# Interfaces.net
KiCad netlist of a schematic drawn in Altium Designer
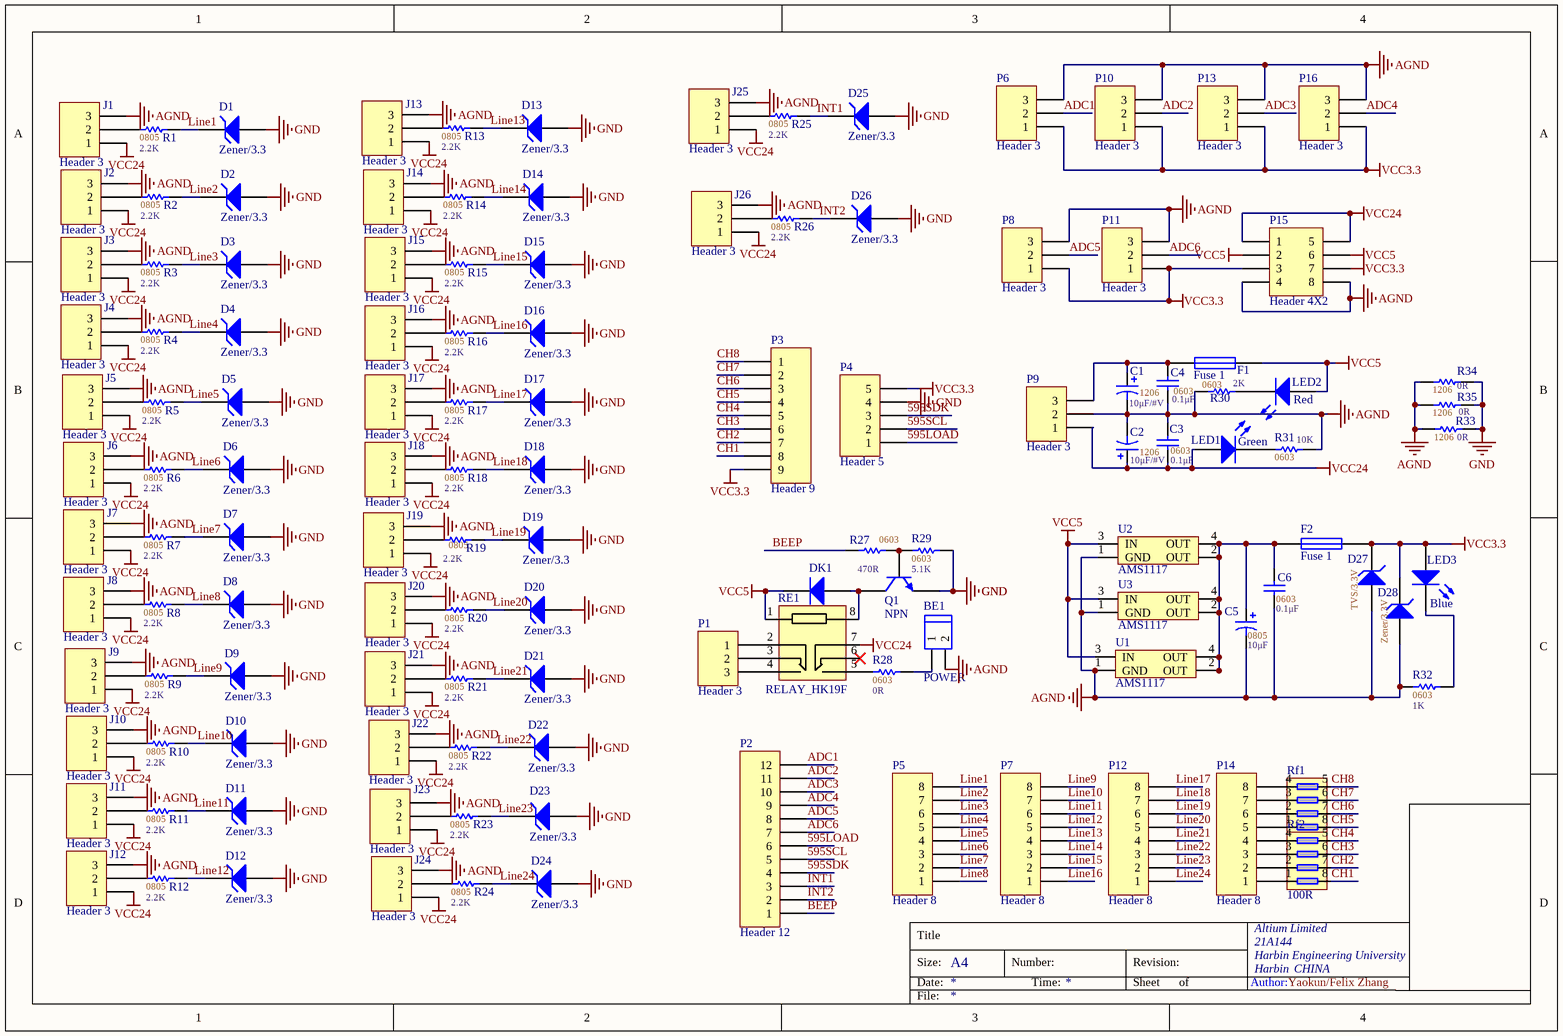
[diagram p0: Interfaces.SchDoc]

(export (version "E")
  (design (tool "Eeschema 10.0.6"))
  (components
    (comp (ref "BE1")
      (value "POWER")
      (footprint "H2_Push_out3.81")
      (libsource (lib "Belong_to_Kongkong") (part "HEAD2"))
    )
    (comp (ref "C1")
      (value "10μF/#V")
      (footprint "CAP_1206")
      (description "Polarized Capacitor (Axial)")
      (fields (field (name "PACKAGEREFERENCE") "1206") (field (name "Comment") "Polar"))
      (libsource (lib "Belong_to_Kongkong") (part "Cap Pol"))
    )
    (comp (ref "C2")
      (value "10μF/#V")
      (footprint "CAP_1206")
      (description "Polarized Capacitor (Axial)")
      (fields (field (name "PACKAGEREFERENCE") "1206") (field (name "Comment") "Polar"))
      (libsource (lib "Belong_to_Kongkong") (part "Cap Pol"))
    )
    (comp (ref "C3")
      (value "0.1μF")
      (footprint "CAP_0603_16*08")
      (description "Capacitor")
      (fields (field (name "PACKAGEREFERENCE") "0603") (field (name "Comment") "0603"))
      (libsource (lib "Belong_to_Kongkong") (part "Cap"))
    )
    (comp (ref "C4")
      (value "0.1μF")
      (footprint "CAP_0603_16*08")
      (description "Capacitor")
      (fields (field (name "PACKAGEREFERENCE") "0603") (field (name "Comment") "0603"))
      (libsource (lib "Belong_to_Kongkong") (part "Cap"))
    )
    (comp (ref "C5")
      (value "10μF")
      (footprint "CAP_0805_20*12")
      (description "Polarized Capacitor (Axial)")
      (fields (field (name "PACKAGEREFERENCE") "0805") (field (name "Comment") "Polar"))
      (libsource (lib "Belong_to_Kongkong") (part "Cap Pol"))
    )
    (comp (ref "C6")
      (value "0.1μF")
      (footprint "CAP_0603_16*08")
      (description "Capacitor")
      (fields (field (name "PACKAGEREFERENCE") "0603") (field (name "Comment") "0603"))
      (libsource (lib "Belong_to_Kongkong") (part "Cap"))
    )
    (comp (ref "D1")
      (value "Zener/3.3")
      (footprint "SOD323")
      (description "Zener Diode")
      (libsource (lib "Belong_to_Kongkong") (part "D Zener"))
    )
    (comp (ref "D2")
      (value "Zener/3.3")
      (footprint "SOD323")
      (description "Zener Diode")
      (libsource (lib "Belong_to_Kongkong") (part "D Zener"))
    )
    (comp (ref "D3")
      (value "Zener/3.3")
      (footprint "SOD323")
      (description "Zener Diode")
      (libsource (lib "Belong_to_Kongkong") (part "D Zener"))
    )
    (comp (ref "D4")
      (value "Zener/3.3")
      (footprint "SOD323")
      (description "Zener Diode")
      (libsource (lib "Belong_to_Kongkong") (part "D Zener"))
    )
    (comp (ref "D5")
      (value "Zener/3.3")
      (footprint "SOD323")
      (description "Zener Diode")
      (libsource (lib "Belong_to_Kongkong") (part "D Zener"))
    )
    (comp (ref "D6")
      (value "Zener/3.3")
      (footprint "SOD323")
      (description "Zener Diode")
      (libsource (lib "Belong_to_Kongkong") (part "D Zener"))
    )
    (comp (ref "D7")
      (value "Zener/3.3")
      (footprint "SOD323")
      (description "Zener Diode")
      (libsource (lib "Belong_to_Kongkong") (part "D Zener"))
    )
    (comp (ref "D8")
      (value "Zener/3.3")
      (footprint "SOD323")
      (description "Zener Diode")
      (libsource (lib "Belong_to_Kongkong") (part "D Zener"))
    )
    (comp (ref "D9")
      (value "Zener/3.3")
      (footprint "SOD323")
      (description "Zener Diode")
      (libsource (lib "Belong_to_Kongkong") (part "D Zener"))
    )
    (comp (ref "D10")
      (value "Zener/3.3")
      (footprint "SOD323")
      (description "Zener Diode")
      (libsource (lib "Belong_to_Kongkong") (part "D Zener"))
    )
    (comp (ref "D11")
      (value "Zener/3.3")
      (footprint "SOD323")
      (description "Zener Diode")
      (libsource (lib "Belong_to_Kongkong") (part "D Zener"))
    )
    (comp (ref "D12")
      (value "Zener/3.3")
      (footprint "SOD323")
      (description "Zener Diode")
      (libsource (lib "Belong_to_Kongkong") (part "D Zener"))
    )
    (comp (ref "D13")
      (value "Zener/3.3")
      (footprint "SOD323")
      (description "Zener Diode")
      (libsource (lib "Belong_to_Kongkong") (part "D Zener"))
    )
    (comp (ref "D14")
      (value "Zener/3.3")
      (footprint "SOD323")
      (description "Zener Diode")
      (libsource (lib "Belong_to_Kongkong") (part "D Zener"))
    )
    (comp (ref "D15")
      (value "Zener/3.3")
      (footprint "SOD323")
      (description "Zener Diode")
      (libsource (lib "Belong_to_Kongkong") (part "D Zener"))
    )
    (comp (ref "D16")
      (value "Zener/3.3")
      (footprint "SOD323")
      (description "Zener Diode")
      (libsource (lib "Belong_to_Kongkong") (part "D Zener"))
    )
    (comp (ref "D17")
      (value "Zener/3.3")
      (footprint "SOD323")
      (description "Zener Diode")
      (libsource (lib "Belong_to_Kongkong") (part "D Zener"))
    )
    (comp (ref "D18")
      (value "Zener/3.3")
      (footprint "SOD323")
      (description "Zener Diode")
      (libsource (lib "Belong_to_Kongkong") (part "D Zener"))
    )
    (comp (ref "D19")
      (value "Zener/3.3")
      (footprint "SOD323")
      (description "Zener Diode")
      (libsource (lib "Belong_to_Kongkong") (part "D Zener"))
    )
    (comp (ref "D20")
      (value "Zener/3.3")
      (footprint "SOD323")
      (description "Zener Diode")
      (libsource (lib "Belong_to_Kongkong") (part "D Zener"))
    )
    (comp (ref "D21")
      (value "Zener/3.3")
      (footprint "SOD323")
      (description "Zener Diode")
      (libsource (lib "Belong_to_Kongkong") (part "D Zener"))
    )
    (comp (ref "D22")
      (value "Zener/3.3")
      (footprint "SOD323")
      (description "Zener Diode")
      (libsource (lib "Belong_to_Kongkong") (part "D Zener"))
    )
    (comp (ref "D23")
      (value "Zener/3.3")
      (footprint "SOD323")
      (description "Zener Diode")
      (libsource (lib "Belong_to_Kongkong") (part "D Zener"))
    )
    (comp (ref "D24")
      (value "Zener/3.3")
      (footprint "SOD323")
      (description "Zener Diode")
      (libsource (lib "Belong_to_Kongkong") (part "D Zener"))
    )
    (comp (ref "D25")
      (value "Zener/3.3")
      (footprint "SOD323")
      (description "Zener Diode")
      (libsource (lib "Belong_to_Kongkong") (part "D Zener"))
    )
    (comp (ref "D26")
      (value "Zener/3.3")
      (footprint "SOD323")
      (description "Zener Diode")
      (libsource (lib "Belong_to_Kongkong") (part "D Zener"))
    )
    (comp (ref "D27")
      (value "TVS/3.3V")
      (footprint "SOD523")
      (description "Zener Diode")
      (libsource (lib "Belong_to_Kongkong") (part "D Zener"))
    )
    (comp (ref "D28")
      (value "Zener/3.3V")
      (footprint "SOD323")
      (description "Zener Diode")
      (libsource (lib "Belong_to_Kongkong") (part "D Zener"))
    )
    (comp (ref "DK1")
      (value "Diode")
      (footprint "Diode1206")
      (description "Default Diode")
      (libsource (lib "Belong_to_Kongkong") (part "Diode"))
    )
    (comp (ref "F1")
      (value "Fuse 1")
      (footprint "FUSE3.5*5.5")
      (description "Fuse")
      (libsource (lib "Belong_to_Kongkong") (part "Fuse 1"))
    )
    (comp (ref "F2")
      (value "Fuse 1")
      (footprint "FUSE3.5*5.5")
      (description "Fuse")
      (libsource (lib "Belong_to_Kongkong") (part "Fuse 1"))
    )
    (comp (ref "J1")
      (value "Header 3")
      (footprint "P3_OUT")
      (description "Header, 3-Pin")
      (libsource (lib "Belong_to_Kongkong") (part "Header 3"))
    )
    (comp (ref "J2")
      (value "Header 3")
      (footprint "P3_OUT")
      (description "Header, 3-Pin")
      (libsource (lib "Belong_to_Kongkong") (part "Header 3"))
    )
    (comp (ref "J3")
      (value "Header 3")
      (footprint "P3_OUT")
      (description "Header, 3-Pin")
      (libsource (lib "Belong_to_Kongkong") (part "Header 3"))
    )
    (comp (ref "J4")
      (value "Header 3")
      (footprint "P3_OUT")
      (description "Header, 3-Pin")
      (libsource (lib "Belong_to_Kongkong") (part "Header 3"))
    )
    (comp (ref "J5")
      (value "Header 3")
      (footprint "P3_OUT")
      (description "Header, 3-Pin")
      (libsource (lib "Belong_to_Kongkong") (part "Header 3"))
    )
    (comp (ref "J6")
      (value "Header 3")
      (footprint "P3_OUT")
      (description "Header, 3-Pin")
      (libsource (lib "Belong_to_Kongkong") (part "Header 3"))
    )
    (comp (ref "J7")
      (value "Header 3")
      (footprint "P3_OUT")
      (description "Header, 3-Pin")
      (libsource (lib "Belong_to_Kongkong") (part "Header 3"))
    )
    (comp (ref "J8")
      (value "Header 3")
      (footprint "P3_OUT")
      (description "Header, 3-Pin")
      (libsource (lib "Belong_to_Kongkong") (part "Header 3"))
    )
    (comp (ref "J9")
      (value "Header 3")
      (footprint "P3_OUT")
      (description "Header, 3-Pin")
      (libsource (lib "Belong_to_Kongkong") (part "Header 3"))
    )
    (comp (ref "J10")
      (value "Header 3")
      (footprint "P3_OUT")
      (description "Header, 3-Pin")
      (libsource (lib "Belong_to_Kongkong") (part "Header 3"))
    )
    (comp (ref "J11")
      (value "Header 3")
      (footprint "P3_OUT")
      (description "Header, 3-Pin")
      (libsource (lib "Belong_to_Kongkong") (part "Header 3"))
    )
    (comp (ref "J12")
      (value "Header 3")
      (footprint "P3_OUT")
      (description "Header, 3-Pin")
      (libsource (lib "Belong_to_Kongkong") (part "Header 3"))
    )
    (comp (ref "J13")
      (value "Header 3")
      (footprint "P3_OUT")
      (description "Header, 3-Pin")
      (libsource (lib "Belong_to_Kongkong") (part "Header 3"))
    )
    (comp (ref "J14")
      (value "Header 3")
      (footprint "P3_OUT")
      (description "Header, 3-Pin")
      (libsource (lib "Belong_to_Kongkong") (part "Header 3"))
    )
    (comp (ref "J15")
      (value "Header 3")
      (footprint "P3_OUT")
      (description "Header, 3-Pin")
      (libsource (lib "Belong_to_Kongkong") (part "Header 3"))
    )
    (comp (ref "J16")
      (value "Header 3")
      (footprint "P3_OUT")
      (description "Header, 3-Pin")
      (libsource (lib "Belong_to_Kongkong") (part "Header 3"))
    )
    (comp (ref "J17")
      (value "Header 3")
      (footprint "P3_OUT")
      (description "Header, 3-Pin")
      (libsource (lib "Belong_to_Kongkong") (part "Header 3"))
    )
    (comp (ref "J18")
      (value "Header 3")
      (footprint "P3")
      (description "Header, 3-Pin")
      (libsource (lib "Belong_to_Kongkong") (part "Header 3"))
    )
    (comp (ref "J19")
      (value "Header 3")
      (footprint "P3")
      (description "Header, 3-Pin")
      (libsource (lib "Belong_to_Kongkong") (part "Header 3"))
    )
    (comp (ref "J20")
      (value "Header 3")
      (footprint "P3")
      (description "Header, 3-Pin")
      (libsource (lib "Belong_to_Kongkong") (part "Header 3"))
    )
    (comp (ref "J21")
      (value "Header 3")
      (footprint "P3")
      (description "Header, 3-Pin")
      (libsource (lib "Belong_to_Kongkong") (part "Header 3"))
    )
    (comp (ref "J22")
      (value "Header 3")
      (footprint "P3")
      (description "Header, 3-Pin")
      (libsource (lib "Belong_to_Kongkong") (part "Header 3"))
    )
    (comp (ref "J23")
      (value "Header 3")
      (footprint "P3")
      (description "Header, 3-Pin")
      (libsource (lib "Belong_to_Kongkong") (part "Header 3"))
    )
    (comp (ref "J24")
      (value "Header 3")
      (footprint "P3")
      (description "Header, 3-Pin")
      (libsource (lib "Belong_to_Kongkong") (part "Header 3"))
    )
    (comp (ref "J25")
      (value "Header 3")
      (footprint "P3_OUT")
      (description "Header, 3-Pin")
      (libsource (lib "Belong_to_Kongkong") (part "Header 3"))
    )
    (comp (ref "J26")
      (value "Header 3")
      (footprint "P3_OUT")
      (description "Header, 3-Pin")
      (libsource (lib "Belong_to_Kongkong") (part "Header 3"))
    )
    (comp (ref "LED1")
      (value "Green")
      (footprint "LED_0805")
      (description "Typical RED, GREEN, YELLOW, AMBER GaAs LED")
      (libsource (lib "Belong_to_Kongkong") (part "LED"))
    )
    (comp (ref "LED2")
      (value "Red")
      (footprint "LED_0805")
      (description "Typical RED, GREEN, YELLOW, AMBER GaAs LED")
      (libsource (lib "Belong_to_Kongkong") (part "LED"))
    )
    (comp (ref "LED3")
      (value "Blue")
      (footprint "LED_0805")
      (description "Typical RED, GREEN, YELLOW, AMBER GaAs LED")
      (libsource (lib "Belong_to_Kongkong") (part "LED"))
    )
    (comp (ref "P1")
      (value "Header 3")
      (footprint "P3_OUT")
      (description "Header, 3-Pin")
      (libsource (lib "") (part "Header 3_1"))
    )
    (comp (ref "P2")
      (value "Header 12")
      (footprint "P12_OUT")
      (description "Header, 12-Pin")
      (libsource (lib "Belong_to_Kongkong") (part "Header 12"))
    )
    (comp (ref "P3")
      (value "Header 9")
      (footprint "P9")
      (description "Header, 9-Pin")
      (libsource (lib "Belong_to_Kongkong") (part "Header 9"))
    )
    (comp (ref "P4")
      (value "Header 5")
      (footprint "Header5_KF2510")
      (description "Header, 5-Pin")
      (libsource (lib "Belong_to_Kongkong") (part "Header 5"))
    )
    (comp (ref "P5")
      (value "Header 8")
      (footprint "P8_OUT")
      (description "Header, 8-Pin")
      (libsource (lib "Belong_to_Kongkong") (part "Header 8"))
    )
    (comp (ref "P6")
      (value "Header 3")
      (footprint "P3_OUT")
      (description "Header, 3-Pin")
      (libsource (lib "Belong_to_Kongkong") (part "Header 3"))
    )
    (comp (ref "P7")
      (value "Header 8")
      (footprint "P8_OUT")
      (description "Header, 8-Pin")
      (libsource (lib "Belong_to_Kongkong") (part "Header 8"))
    )
    (comp (ref "P8")
      (value "Header 3")
      (footprint "P3")
      (description "Header, 3-Pin")
      (libsource (lib "Belong_to_Kongkong") (part "Header 3"))
    )
    (comp (ref "P9")
      (value "Header 3")
      (footprint "Header3_HC5.08")
      (description "Header, 3-Pin")
      (libsource (lib "Belong_to_Kongkong") (part "Header 3"))
    )
    (comp (ref "P10")
      (value "Header 3")
      (footprint "P3_OUT")
      (description "Header, 3-Pin")
      (libsource (lib "Belong_to_Kongkong") (part "Header 3"))
    )
    (comp (ref "P11")
      (value "Header 3")
      (footprint "P3")
      (description "Header, 3-Pin")
      (libsource (lib "Belong_to_Kongkong") (part "Header 3"))
    )
    (comp (ref "P12")
      (value "Header 8")
      (footprint "P8_OUT")
      (description "Header, 8-Pin")
      (libsource (lib "Belong_to_Kongkong") (part "Header 8"))
    )
    (comp (ref "P13")
      (value "Header 3")
      (footprint "P3_OUT")
      (description "Header, 3-Pin")
      (libsource (lib "Belong_to_Kongkong") (part "Header 3"))
    )
    (comp (ref "P14")
      (value "Header 8")
      (footprint "P8_OUT")
      (description "Header, 8-Pin")
      (libsource (lib "Belong_to_Kongkong") (part "Header 8"))
    )
    (comp (ref "P15")
      (value "Header 4X2")
      (footprint "HEADER2*4_PIN")
      (description "Header, 4-Pin, Dual row")
      (libsource (lib "Belong_to_Kongkong") (part "Header 4X2"))
    )
    (comp (ref "P16")
      (value "Header 3")
      (footprint "P3_OUT")
      (description "Header, 3-Pin")
      (libsource (lib "Belong_to_Kongkong") (part "Header 3"))
    )
    (comp (ref "Q1")
      (value "NPN")
      (footprint "SOT23_J3Y")
      (description "NPN Bipolar Transistor")
      (libsource (lib "Belong_to_Kongkong") (part "NPN"))
    )
    (comp (ref "R1")
      (value "2.2K")
      (footprint "RES_0805_20*12")
      (description "Resistor")
      (fields (field (name "PACKAGEREFERENCE") "0805") (field (name "Comment") "SMD"))
      (libsource (lib "Belong_to_Kongkong") (part "RES_SMD"))
    )
    (comp (ref "R2")
      (value "2.2K")
      (footprint "RES_0805_20*12")
      (description "Resistor")
      (fields (field (name "PACKAGEREFERENCE") "0805") (field (name "Comment") "SMD"))
      (libsource (lib "Belong_to_Kongkong") (part "RES_SMD"))
    )
    (comp (ref "R3")
      (value "2.2K")
      (footprint "RES_0805_20*12")
      (description "Resistor")
      (fields (field (name "PACKAGEREFERENCE") "0805") (field (name "Comment") "SMD"))
      (libsource (lib "Belong_to_Kongkong") (part "RES_SMD"))
    )
    (comp (ref "R4")
      (value "2.2K")
      (footprint "RES_0805_20*12")
      (description "Resistor")
      (fields (field (name "PACKAGEREFERENCE") "0805") (field (name "Comment") "SMD"))
      (libsource (lib "Belong_to_Kongkong") (part "RES_SMD"))
    )
    (comp (ref "R5")
      (value "2.2K")
      (footprint "RES_0805_20*12")
      (description "Resistor")
      (fields (field (name "PACKAGEREFERENCE") "0805") (field (name "Comment") "SMD"))
      (libsource (lib "Belong_to_Kongkong") (part "RES_SMD"))
    )
    (comp (ref "R6")
      (value "2.2K")
      (footprint "RES_0805_20*12")
      (description "Resistor")
      (fields (field (name "PACKAGEREFERENCE") "0805") (field (name "Comment") "SMD"))
      (libsource (lib "Belong_to_Kongkong") (part "RES_SMD"))
    )
    (comp (ref "R7")
      (value "2.2K")
      (footprint "RES_0805_20*12")
      (description "Resistor")
      (fields (field (name "PACKAGEREFERENCE") "0805") (field (name "Comment") "SMD"))
      (libsource (lib "Belong_to_Kongkong") (part "RES_SMD"))
    )
    (comp (ref "R8")
      (value "2.2K")
      (footprint "RES_0805_20*12")
      (description "Resistor")
      (fields (field (name "PACKAGEREFERENCE") "0805") (field (name "Comment") "SMD"))
      (libsource (lib "Belong_to_Kongkong") (part "RES_SMD"))
    )
    (comp (ref "R9")
      (value "2.2K")
      (footprint "RES_0805_20*12")
      (description "Resistor")
      (fields (field (name "PACKAGEREFERENCE") "0805") (field (name "Comment") "SMD"))
      (libsource (lib "Belong_to_Kongkong") (part "RES_SMD"))
    )
    (comp (ref "R10")
      (value "2.2K")
      (footprint "RES_0805_20*12")
      (description "Resistor")
      (fields (field (name "PACKAGEREFERENCE") "0805") (field (name "Comment") "SMD"))
      (libsource (lib "Belong_to_Kongkong") (part "RES_SMD"))
    )
    (comp (ref "R11")
      (value "2.2K")
      (footprint "RES_0805_20*12")
      (description "Resistor")
      (fields (field (name "PACKAGEREFERENCE") "0805") (field (name "Comment") "SMD"))
      (libsource (lib "Belong_to_Kongkong") (part "RES_SMD"))
    )
    (comp (ref "R12")
      (value "2.2K")
      (footprint "RES_0805_20*12")
      (description "Resistor")
      (fields (field (name "PACKAGEREFERENCE") "0805") (field (name "Comment") "SMD"))
      (libsource (lib "Belong_to_Kongkong") (part "RES_SMD"))
    )
    (comp (ref "R13")
      (value "2.2K")
      (footprint "RES_0805_20*12")
      (description "Resistor")
      (fields (field (name "PACKAGEREFERENCE") "0805") (field (name "Comment") "SMD"))
      (libsource (lib "Belong_to_Kongkong") (part "RES_SMD"))
    )
    (comp (ref "R14")
      (value "2.2K")
      (footprint "RES_0805_20*12")
      (description "Resistor")
      (fields (field (name "PACKAGEREFERENCE") "0805") (field (name "Comment") "SMD"))
      (libsource (lib "Belong_to_Kongkong") (part "RES_SMD"))
    )
    (comp (ref "R15")
      (value "2.2K")
      (footprint "RES_0805_20*12")
      (description "Resistor")
      (fields (field (name "PACKAGEREFERENCE") "0805") (field (name "Comment") "SMD"))
      (libsource (lib "Belong_to_Kongkong") (part "RES_SMD"))
    )
    (comp (ref "R16")
      (value "2.2K")
      (footprint "RES_0805_20*12")
      (description "Resistor")
      (fields (field (name "PACKAGEREFERENCE") "0805") (field (name "Comment") "SMD"))
      (libsource (lib "Belong_to_Kongkong") (part "RES_SMD"))
    )
    (comp (ref "R17")
      (value "2.2K")
      (footprint "RES_0805_20*12")
      (description "Resistor")
      (fields (field (name "PACKAGEREFERENCE") "0805") (field (name "Comment") "SMD"))
      (libsource (lib "Belong_to_Kongkong") (part "RES_SMD"))
    )
    (comp (ref "R18")
      (value "2.2K")
      (footprint "RES_0805_20*12")
      (description "Resistor")
      (fields (field (name "PACKAGEREFERENCE") "0805") (field (name "Comment") "SMD"))
      (libsource (lib "Belong_to_Kongkong") (part "RES_SMD"))
    )
    (comp (ref "R19")
      (value "2.2K")
      (footprint "RES_0805_20*12")
      (description "Resistor")
      (fields (field (name "PACKAGEREFERENCE") "0805") (field (name "Comment") "SMD"))
      (libsource (lib "Belong_to_Kongkong") (part "RES_SMD"))
    )
    (comp (ref "R20")
      (value "2.2K")
      (footprint "RES_0805_20*12")
      (description "Resistor")
      (fields (field (name "PACKAGEREFERENCE") "0805") (field (name "Comment") "SMD"))
      (libsource (lib "Belong_to_Kongkong") (part "RES_SMD"))
    )
    (comp (ref "R21")
      (value "2.2K")
      (footprint "RES_0805_20*12")
      (description "Resistor")
      (fields (field (name "PACKAGEREFERENCE") "0805") (field (name "Comment") "SMD"))
      (libsource (lib "Belong_to_Kongkong") (part "RES_SMD"))
    )
    (comp (ref "R22")
      (value "2.2K")
      (footprint "RES_0805_20*12")
      (description "Resistor")
      (fields (field (name "PACKAGEREFERENCE") "0805") (field (name "Comment") "SMD"))
      (libsource (lib "Belong_to_Kongkong") (part "RES_SMD"))
    )
    (comp (ref "R23")
      (value "2.2K")
      (footprint "RES_0805_20*12")
      (description "Resistor")
      (fields (field (name "PACKAGEREFERENCE") "0805") (field (name "Comment") "SMD"))
      (libsource (lib "Belong_to_Kongkong") (part "RES_SMD"))
    )
    (comp (ref "R24")
      (value "2.2K")
      (footprint "RES_0805_20*12")
      (description "Resistor")
      (fields (field (name "PACKAGEREFERENCE") "0805") (field (name "Comment") "SMD"))
      (libsource (lib "Belong_to_Kongkong") (part "RES_SMD"))
    )
    (comp (ref "R25")
      (value "2.2K")
      (footprint "RES_0805_20*12")
      (description "Resistor")
      (fields (field (name "PACKAGEREFERENCE") "0805") (field (name "Comment") "SMD"))
      (libsource (lib "Belong_to_Kongkong") (part "RES_SMD"))
    )
    (comp (ref "R26")
      (value "2.2K")
      (footprint "RES_0805_20*12")
      (description "Resistor")
      (fields (field (name "PACKAGEREFERENCE") "0805") (field (name "Comment") "SMD"))
      (libsource (lib "Belong_to_Kongkong") (part "RES_SMD"))
    )
    (comp (ref "R27")
      (value "470R")
      (footprint "RES_0603_16*08")
      (description "Resistor")
      (fields (field (name "PACKAGEREFERENCE") "0603") (field (name "Comment") "SMD"))
      (libsource (lib "Belong_to_Kongkong") (part "RES_SMD"))
    )
    (comp (ref "R28")
      (value "0R")
      (footprint "RES_0805_20*12")
      (description "Resistor")
      (fields (field (name "PACKAGEREFERENCE") "0603") (field (name "Comment") "SMD"))
      (libsource (lib "Belong_to_Kongkong") (part "RES_SMD"))
    )
    (comp (ref "R29")
      (value "5.1K")
      (footprint "RES_0603_16*08")
      (description "Resistor")
      (fields (field (name "PACKAGEREFERENCE") "0603") (field (name "Comment") "SMD"))
      (libsource (lib "Belong_to_Kongkong") (part "RES_SMD"))
    )
    (comp (ref "R30")
      (value "2K")
      (footprint "RES_0805_20*12")
      (description "Resistor")
      (fields (field (name "PACKAGEREFERENCE") "0603") (field (name "Comment") "SMD"))
      (libsource (lib "Belong_to_Kongkong") (part "RES_SMD"))
    )
    (comp (ref "R31")
      (value "10K")
      (footprint "RES_0805_20*12")
      (description "Resistor")
      (fields (field (name "PACKAGEREFERENCE") "0603") (field (name "Comment") "SMD"))
      (libsource (lib "Belong_to_Kongkong") (part "RES_SMD"))
    )
    (comp (ref "R32")
      (value "1K")
      (footprint "RES_0805_20*12")
      (description "Resistor")
      (fields (field (name "PACKAGEREFERENCE") "0603") (field (name "Comment") "SMD"))
      (libsource (lib "Belong_to_Kongkong") (part "RES_SMD"))
    )
    (comp (ref "R33")
      (value "0R")
      (footprint "RES_1206")
      (description "Resistor")
      (fields (field (name "PACKAGEREFERENCE") "1206") (field (name "Comment") "SMD"))
      (libsource (lib "Belong_to_Kongkong") (part "RES_SMD"))
    )
    (comp (ref "R34")
      (value "0R")
      (footprint "RES_1206")
      (description "Resistor")
      (fields (field (name "PACKAGEREFERENCE") "1206") (field (name "Comment") "SMD"))
      (libsource (lib "Belong_to_Kongkong") (part "RES_SMD"))
    )
    (comp (ref "R35")
      (value "0R")
      (footprint "RES_1206")
      (description "Resistor")
      (fields (field (name "PACKAGEREFERENCE") "1206") (field (name "Comment") "SMD"))
      (libsource (lib "Belong_to_Kongkong") (part "RES_SMD"))
    )
    (comp (ref "RE1")
      (value "RELAY_HK19F")
      (footprint "Relay_HK19F")
      (libsource (lib "Belong_to_Kongkong") (part "RELAY_HK19F"))
    )
    (comp (ref "Rf1")
      (value "100R")
      (footprint "RES_FOUR_0603")
      (libsource (lib "Belong_to_Kongkong") (part "RES_4P"))
    )
    (comp (ref "Rf2")
      (value "100R")
      (footprint "RES_FOUR_0603")
      (libsource (lib "Belong_to_Kongkong") (part "RES_4P"))
    )
    (comp (ref "U1")
      (value "AMS1117")
      (footprint "SOT223_M")
      (libsource (lib "Belong_to_Kongkong") (part "AMS1117"))
    )
    (comp (ref "U2")
      (value "AMS1117")
      (footprint "SOT223_M")
      (libsource (lib "Belong_to_Kongkong") (part "AMS1117"))
    )
    (comp (ref "U3")
      (value "AMS1117")
      (footprint "SOT223_M")
      (libsource (lib "Belong_to_Kongkong") (part "AMS1117"))
    )
  )
  (nets
    (net (code "1") (name "/595LOAD") (class "Default")
      (node (ref "P2") (pin "6") (pinfunction "6_6") (pintype "passive"))
      (node (ref "P4") (pin "1") (pinfunction "1_1") (pintype "passive"))
    )
    (net (code "2") (name "/595SCL") (class "Default")
      (node (ref "P2") (pin "5") (pinfunction "5_5") (pintype "passive"))
      (node (ref "P4") (pin "2") (pinfunction "2_2") (pintype "passive"))
    )
    (net (code "3") (name "/595SDK") (class "Default")
      (node (ref "P2") (pin "4") (pinfunction "4_4") (pintype "passive"))
      (node (ref "P4") (pin "3") (pinfunction "3_3") (pintype "passive"))
    )
    (net (code "4") (name "/ADC1") (class "Default")
      (node (ref "P2") (pin "12") (pinfunction "12_12") (pintype "passive"))
      (node (ref "P6") (pin "2") (pinfunction "2_2") (pintype "passive"))
    )
    (net (code "5") (name "/ADC2") (class "Default")
      (node (ref "P10") (pin "2") (pinfunction "2_2") (pintype "passive"))
      (node (ref "P2") (pin "11") (pinfunction "11_11") (pintype "passive"))
    )
    (net (code "6") (name "/ADC3") (class "Default")
      (node (ref "P13") (pin "2") (pinfunction "2_2") (pintype "passive"))
      (node (ref "P2") (pin "10") (pinfunction "10_10") (pintype "passive"))
    )
    (net (code "7") (name "/ADC4") (class "Default")
      (node (ref "P16") (pin "2") (pinfunction "2_2") (pintype "passive"))
      (node (ref "P2") (pin "9") (pinfunction "9_9") (pintype "passive"))
    )
    (net (code "8") (name "/ADC5") (class "Default")
      (node (ref "P2") (pin "8") (pinfunction "8_8") (pintype "passive"))
      (node (ref "P8") (pin "2") (pinfunction "2_2") (pintype "passive"))
    )
    (net (code "9") (name "/ADC6") (class "Default")
      (node (ref "P11") (pin "2") (pinfunction "2_2") (pintype "passive"))
      (node (ref "P2") (pin "7") (pinfunction "7_7") (pintype "passive"))
    )
    (net (code "10") (name "/BEEP") (class "Default")
      (node (ref "P2") (pin "1") (pinfunction "1_1") (pintype "passive"))
      (node (ref "R27") (pin "1") (pinfunction "1_1") (pintype "passive"))
    )
    (net (code "11") (name "/CH1") (class "Default")
      (node (ref "P3") (pin "8") (pinfunction "8_8") (pintype "passive"))
      (node (ref "Rf2") (pin "8") (pinfunction "8_8") (pintype "passive"))
    )
    (net (code "12") (name "/CH2") (class "Default")
      (node (ref "P3") (pin "7") (pinfunction "7_7") (pintype "passive"))
      (node (ref "Rf2") (pin "7") (pinfunction "7_7") (pintype "passive"))
    )
    (net (code "13") (name "/CH3") (class "Default")
      (node (ref "P3") (pin "6") (pinfunction "6_6") (pintype "passive"))
      (node (ref "Rf2") (pin "6") (pinfunction "6_6") (pintype "passive"))
    )
    (net (code "14") (name "/CH4") (class "Default")
      (node (ref "P3") (pin "5") (pinfunction "5_5") (pintype "passive"))
      (node (ref "Rf2") (pin "5") (pinfunction "5_5") (pintype "passive"))
    )
    (net (code "15") (name "/CH5") (class "Default")
      (node (ref "P3") (pin "4") (pinfunction "4_4") (pintype "passive"))
      (node (ref "Rf1") (pin "8") (pinfunction "8_8") (pintype "passive"))
    )
    (net (code "16") (name "/CH6") (class "Default")
      (node (ref "P3") (pin "3") (pinfunction "3_3") (pintype "passive"))
      (node (ref "Rf1") (pin "7") (pinfunction "7_7") (pintype "passive"))
    )
    (net (code "17") (name "/CH7") (class "Default")
      (node (ref "P3") (pin "2") (pinfunction "2_2") (pintype "passive"))
      (node (ref "Rf1") (pin "6") (pinfunction "6_6") (pintype "passive"))
    )
    (net (code "18") (name "/CH8") (class "Default")
      (node (ref "P3") (pin "1") (pinfunction "1_1") (pintype "passive"))
      (node (ref "Rf1") (pin "5") (pinfunction "5_5") (pintype "passive"))
    )
    (net (code "19") (name "/INT1") (class "Default")
      (node (ref "D25") (pin "2") (pinfunction "K_2") (pintype "passive"))
      (node (ref "P2") (pin "3") (pinfunction "3_3") (pintype "passive"))
      (node (ref "R25") (pin "1") (pinfunction "1_1") (pintype "passive"))
    )
    (net (code "20") (name "/INT2") (class "Default")
      (node (ref "D26") (pin "2") (pinfunction "K_2") (pintype "passive"))
      (node (ref "P2") (pin "2") (pinfunction "2_2") (pintype "passive"))
      (node (ref "R26") (pin "1") (pinfunction "1_1") (pintype "passive"))
    )
    (net (code "21") (name "/Line1") (class "Default")
      (node (ref "D1") (pin "2") (pinfunction "K_2") (pintype "passive"))
      (node (ref "P5") (pin "8") (pinfunction "8_8") (pintype "passive"))
      (node (ref "R1") (pin "1") (pinfunction "1_1") (pintype "passive"))
    )
    (net (code "22") (name "/Line2") (class "Default")
      (node (ref "D2") (pin "2") (pinfunction "K_2") (pintype "passive"))
      (node (ref "P5") (pin "7") (pinfunction "7_7") (pintype "passive"))
      (node (ref "R2") (pin "1") (pinfunction "1_1") (pintype "passive"))
    )
    (net (code "23") (name "/Line3") (class "Default")
      (node (ref "D3") (pin "2") (pinfunction "K_2") (pintype "passive"))
      (node (ref "P5") (pin "6") (pinfunction "6_6") (pintype "passive"))
      (node (ref "R3") (pin "1") (pinfunction "1_1") (pintype "passive"))
    )
    (net (code "24") (name "/Line4") (class "Default")
      (node (ref "D4") (pin "2") (pinfunction "K_2") (pintype "passive"))
      (node (ref "P5") (pin "5") (pinfunction "5_5") (pintype "passive"))
      (node (ref "R4") (pin "1") (pinfunction "1_1") (pintype "passive"))
    )
    (net (code "25") (name "/Line5") (class "Default")
      (node (ref "D5") (pin "2") (pinfunction "K_2") (pintype "passive"))
      (node (ref "P5") (pin "4") (pinfunction "4_4") (pintype "passive"))
      (node (ref "R5") (pin "1") (pinfunction "1_1") (pintype "passive"))
    )
    (net (code "26") (name "/Line6") (class "Default")
      (node (ref "D6") (pin "2") (pinfunction "K_2") (pintype "passive"))
      (node (ref "P5") (pin "3") (pinfunction "3_3") (pintype "passive"))
      (node (ref "R6") (pin "1") (pinfunction "1_1") (pintype "passive"))
    )
    (net (code "27") (name "/Line7") (class "Default")
      (node (ref "D7") (pin "2") (pinfunction "K_2") (pintype "passive"))
      (node (ref "P5") (pin "2") (pinfunction "2_2") (pintype "passive"))
      (node (ref "R7") (pin "1") (pinfunction "1_1") (pintype "passive"))
    )
    (net (code "28") (name "/Line8") (class "Default")
      (node (ref "D8") (pin "2") (pinfunction "K_2") (pintype "passive"))
      (node (ref "P5") (pin "1") (pinfunction "1_1") (pintype "passive"))
      (node (ref "R8") (pin "1") (pinfunction "1_1") (pintype "passive"))
    )
    (net (code "29") (name "/Line9") (class "Default")
      (node (ref "D9") (pin "2") (pinfunction "K_2") (pintype "passive"))
      (node (ref "P7") (pin "8") (pinfunction "8_8") (pintype "passive"))
      (node (ref "R9") (pin "1") (pinfunction "1_1") (pintype "passive"))
    )
    (net (code "30") (name "/Line10") (class "Default")
      (node (ref "D10") (pin "2") (pinfunction "K_2") (pintype "passive"))
      (node (ref "P7") (pin "7") (pinfunction "7_7") (pintype "passive"))
      (node (ref "R10") (pin "1") (pinfunction "1_1") (pintype "passive"))
    )
    (net (code "31") (name "/Line11") (class "Default")
      (node (ref "D11") (pin "2") (pinfunction "K_2") (pintype "passive"))
      (node (ref "P7") (pin "6") (pinfunction "6_6") (pintype "passive"))
      (node (ref "R11") (pin "1") (pinfunction "1_1") (pintype "passive"))
    )
    (net (code "32") (name "/Line12") (class "Default")
      (node (ref "D12") (pin "2") (pinfunction "K_2") (pintype "passive"))
      (node (ref "P7") (pin "5") (pinfunction "5_5") (pintype "passive"))
      (node (ref "R12") (pin "1") (pinfunction "1_1") (pintype "passive"))
    )
    (net (code "33") (name "/Line13") (class "Default")
      (node (ref "D13") (pin "2") (pinfunction "K_2") (pintype "passive"))
      (node (ref "P7") (pin "4") (pinfunction "4_4") (pintype "passive"))
      (node (ref "R13") (pin "1") (pinfunction "1_1") (pintype "passive"))
    )
    (net (code "34") (name "/Line14") (class "Default")
      (node (ref "D14") (pin "2") (pinfunction "K_2") (pintype "passive"))
      (node (ref "P7") (pin "3") (pinfunction "3_3") (pintype "passive"))
      (node (ref "R14") (pin "1") (pinfunction "1_1") (pintype "passive"))
    )
    (net (code "35") (name "/Line15") (class "Default")
      (node (ref "D15") (pin "2") (pinfunction "K_2") (pintype "passive"))
      (node (ref "P7") (pin "2") (pinfunction "2_2") (pintype "passive"))
      (node (ref "R15") (pin "1") (pinfunction "1_1") (pintype "passive"))
    )
    (net (code "36") (name "/Line16") (class "Default")
      (node (ref "D16") (pin "2") (pinfunction "K_2") (pintype "passive"))
      (node (ref "P7") (pin "1") (pinfunction "1_1") (pintype "passive"))
      (node (ref "R16") (pin "1") (pinfunction "1_1") (pintype "passive"))
    )
    (net (code "37") (name "/Line17") (class "Default")
      (node (ref "D17") (pin "2") (pinfunction "K_2") (pintype "passive"))
      (node (ref "P12") (pin "8") (pinfunction "8_8") (pintype "passive"))
      (node (ref "R17") (pin "1") (pinfunction "1_1") (pintype "passive"))
    )
    (net (code "38") (name "/Line18") (class "Default")
      (node (ref "D18") (pin "2") (pinfunction "K_2") (pintype "passive"))
      (node (ref "P12") (pin "7") (pinfunction "7_7") (pintype "passive"))
      (node (ref "R18") (pin "1") (pinfunction "1_1") (pintype "passive"))
    )
    (net (code "39") (name "/Line19") (class "Default")
      (node (ref "D19") (pin "2") (pinfunction "K_2") (pintype "passive"))
      (node (ref "P12") (pin "6") (pinfunction "6_6") (pintype "passive"))
      (node (ref "R19") (pin "1") (pinfunction "1_1") (pintype "passive"))
    )
    (net (code "40") (name "/Line20") (class "Default")
      (node (ref "D20") (pin "2") (pinfunction "K_2") (pintype "passive"))
      (node (ref "P12") (pin "5") (pinfunction "5_5") (pintype "passive"))
      (node (ref "R20") (pin "1") (pinfunction "1_1") (pintype "passive"))
    )
    (net (code "41") (name "/Line21") (class "Default")
      (node (ref "D21") (pin "2") (pinfunction "K_2") (pintype "passive"))
      (node (ref "P12") (pin "4") (pinfunction "4_4") (pintype "passive"))
      (node (ref "R21") (pin "1") (pinfunction "1_1") (pintype "passive"))
    )
    (net (code "42") (name "/Line22") (class "Default")
      (node (ref "D22") (pin "2") (pinfunction "K_2") (pintype "passive"))
      (node (ref "P12") (pin "3") (pinfunction "3_3") (pintype "passive"))
      (node (ref "R22") (pin "1") (pinfunction "1_1") (pintype "passive"))
    )
    (net (code "43") (name "/Line23") (class "Default")
      (node (ref "D23") (pin "2") (pinfunction "K_2") (pintype "passive"))
      (node (ref "P12") (pin "2") (pinfunction "2_2") (pintype "passive"))
      (node (ref "R23") (pin "1") (pinfunction "1_1") (pintype "passive"))
    )
    (net (code "44") (name "/Line24") (class "Default")
      (node (ref "D24") (pin "2") (pinfunction "K_2") (pintype "passive"))
      (node (ref "P12") (pin "1") (pinfunction "1_1") (pintype "passive"))
      (node (ref "R24") (pin "1") (pinfunction "1_1") (pintype "passive"))
    )
    (net (code "45") (name "AGND") (class "Default")
      (node (ref "BE1") (pin "2") (pinfunction "2_2") (pintype "passive"))
      (node (ref "C1") (pin "2") (pinfunction "2_2") (pintype "passive"))
      (node (ref "C2") (pin "2") (pinfunction "2_2") (pintype "passive"))
      (node (ref "C3") (pin "2") (pinfunction "2_2") (pintype "passive"))
      (node (ref "C4") (pin "1") (pinfunction "1_1") (pintype "passive"))
      (node (ref "C5") (pin "2") (pinfunction "2_2") (pintype "passive"))
      (node (ref "C6") (pin "1") (pinfunction "1_1") (pintype "passive"))
      (node (ref "D27") (pin "1") (pinfunction "A_1") (pintype "passive"))
      (node (ref "D28") (pin "1") (pinfunction "A_1") (pintype "passive"))
      (node (ref "J1") (pin "3") (pinfunction "3_3") (pintype "passive"))
      (node (ref "J10") (pin "3") (pinfunction "3_3") (pintype "passive"))
      (node (ref "J11") (pin "3") (pinfunction "3_3") (pintype "passive"))
      (node (ref "J12") (pin "3") (pinfunction "3_3") (pintype "passive"))
      (node (ref "J13") (pin "3") (pinfunction "3_3") (pintype "passive"))
      (node (ref "J14") (pin "3") (pinfunction "3_3") (pintype "passive"))
      (node (ref "J15") (pin "3") (pinfunction "3_3") (pintype "passive"))
      (node (ref "J16") (pin "3") (pinfunction "3_3") (pintype "passive"))
      (node (ref "J17") (pin "3") (pinfunction "3_3") (pintype "passive"))
      (node (ref "J18") (pin "3") (pinfunction "3_3") (pintype "passive"))
      (node (ref "J19") (pin "3") (pinfunction "3_3") (pintype "passive"))
      (node (ref "J2") (pin "3") (pinfunction "3_3") (pintype "passive"))
      (node (ref "J20") (pin "3") (pinfunction "3_3") (pintype "passive"))
      (node (ref "J21") (pin "3") (pinfunction "3_3") (pintype "passive"))
      (node (ref "J22") (pin "3") (pinfunction "3_3") (pintype "passive"))
      (node (ref "J23") (pin "3") (pinfunction "3_3") (pintype "passive"))
      (node (ref "J24") (pin "3") (pinfunction "3_3") (pintype "passive"))
      (node (ref "J25") (pin "3") (pinfunction "3_3") (pintype "passive"))
      (node (ref "J26") (pin "3") (pinfunction "3_3") (pintype "passive"))
      (node (ref "J3") (pin "3") (pinfunction "3_3") (pintype "passive"))
      (node (ref "J4") (pin "3") (pinfunction "3_3") (pintype "passive"))
      (node (ref "J5") (pin "3") (pinfunction "3_3") (pintype "passive"))
      (node (ref "J6") (pin "3") (pinfunction "3_3") (pintype "passive"))
      (node (ref "J7") (pin "3") (pinfunction "3_3") (pintype "passive"))
      (node (ref "J8") (pin "3") (pinfunction "3_3") (pintype "passive"))
      (node (ref "J9") (pin "3") (pinfunction "3_3") (pintype "passive"))
      (node (ref "P10") (pin "3") (pinfunction "3_3") (pintype "passive"))
      (node (ref "P11") (pin "3") (pinfunction "3_3") (pintype "passive"))
      (node (ref "P13") (pin "3") (pinfunction "3_3") (pintype "passive"))
      (node (ref "P15") (pin "4") (pinfunction "4_4") (pintype "passive"))
      (node (ref "P15") (pin "8") (pinfunction "8_8") (pintype "passive"))
      (node (ref "P16") (pin "3") (pinfunction "3_3") (pintype "passive"))
      (node (ref "P6") (pin "3") (pinfunction "3_3") (pintype "passive"))
      (node (ref "P8") (pin "3") (pinfunction "3_3") (pintype "passive"))
      (node (ref "P9") (pin "2") (pinfunction "2_2") (pintype "passive"))
      (node (ref "R30") (pin "1") (pinfunction "1_1") (pintype "passive"))
      (node (ref "R31") (pin "2") (pinfunction "2_2") (pintype "passive"))
      (node (ref "R32") (pin "2") (pinfunction "2_2") (pintype "passive"))
      (node (ref "R33") (pin "1") (pinfunction "1_1") (pintype "passive"))
      (node (ref "R34") (pin "1") (pinfunction "1_1") (pintype "passive"))
      (node (ref "R35") (pin "1") (pinfunction "1_1") (pintype "passive"))
      (node (ref "U1") (pin "1") (pinfunction "GND_1") (pintype "passive"))
      (node (ref "U2") (pin "1") (pinfunction "GND_1") (pintype "passive"))
      (node (ref "U3") (pin "1") (pinfunction "GND_1") (pintype "passive"))
    )
    (net (code "46") (name "GND") (class "Default")
      (node (ref "D1") (pin "1") (pinfunction "A_1") (pintype "passive"))
      (node (ref "D10") (pin "1") (pinfunction "A_1") (pintype "passive"))
      (node (ref "D11") (pin "1") (pinfunction "A_1") (pintype "passive"))
      (node (ref "D12") (pin "1") (pinfunction "A_1") (pintype "passive"))
      (node (ref "D13") (pin "1") (pinfunction "A_1") (pintype "passive"))
      (node (ref "D14") (pin "1") (pinfunction "A_1") (pintype "passive"))
      (node (ref "D15") (pin "1") (pinfunction "A_1") (pintype "passive"))
      (node (ref "D16") (pin "1") (pinfunction "A_1") (pintype "passive"))
      (node (ref "D17") (pin "1") (pinfunction "A_1") (pintype "passive"))
      (node (ref "D18") (pin "1") (pinfunction "A_1") (pintype "passive"))
      (node (ref "D19") (pin "1") (pinfunction "A_1") (pintype "passive"))
      (node (ref "D2") (pin "1") (pinfunction "A_1") (pintype "passive"))
      (node (ref "D20") (pin "1") (pinfunction "A_1") (pintype "passive"))
      (node (ref "D21") (pin "1") (pinfunction "A_1") (pintype "passive"))
      (node (ref "D22") (pin "1") (pinfunction "A_1") (pintype "passive"))
      (node (ref "D23") (pin "1") (pinfunction "A_1") (pintype "passive"))
      (node (ref "D24") (pin "1") (pinfunction "A_1") (pintype "passive"))
      (node (ref "D25") (pin "1") (pinfunction "A_1") (pintype "passive"))
      (node (ref "D26") (pin "1") (pinfunction "A_1") (pintype "passive"))
      (node (ref "D3") (pin "1") (pinfunction "A_1") (pintype "passive"))
      (node (ref "D4") (pin "1") (pinfunction "A_1") (pintype "passive"))
      (node (ref "D5") (pin "1") (pinfunction "A_1") (pintype "passive"))
      (node (ref "D6") (pin "1") (pinfunction "A_1") (pintype "passive"))
      (node (ref "D7") (pin "1") (pinfunction "A_1") (pintype "passive"))
      (node (ref "D8") (pin "1") (pinfunction "A_1") (pintype "passive"))
      (node (ref "D9") (pin "1") (pinfunction "A_1") (pintype "passive"))
      (node (ref "P4") (pin "4") (pinfunction "4_4") (pintype "passive"))
      (node (ref "Q1") (pin "3") (pinfunction "E_3") (pintype "passive"))
      (node (ref "R29") (pin "2") (pinfunction "2_2") (pintype "passive"))
      (node (ref "R33") (pin "2") (pinfunction "2_2") (pintype "passive"))
      (node (ref "R34") (pin "2") (pinfunction "2_2") (pintype "passive"))
      (node (ref "R35") (pin "2") (pinfunction "2_2") (pintype "passive"))
    )
    (net (code "47") (name "Net-(BE1-Pad1)") (class "Default")
      (node (ref "BE1") (pin "1") (pinfunction "1_1") (pintype "passive"))
      (node (ref "R28") (pin "2") (pinfunction "2_2") (pintype "passive"))
    )
    (net (code "48") (name "Net-(C1-Pad1)") (class "Default")
      (node (ref "C1") (pin "1") (pinfunction "1_1") (pintype "passive"))
      (node (ref "C4") (pin "2") (pinfunction "2_2") (pintype "passive"))
      (node (ref "F1") (pin "1") (pinfunction "1_1") (pintype "passive"))
      (node (ref "P9") (pin "3") (pinfunction "3_3") (pintype "passive"))
    )
    (net (code "49") (name "Net-(C5-Pad1)") (class "Default")
      (node (ref "C5") (pin "1") (pinfunction "1_1") (pintype "passive"))
      (node (ref "C6") (pin "2") (pinfunction "2_2") (pintype "passive"))
      (node (ref "F2") (pin "1") (pinfunction "1_1") (pintype "passive"))
      (node (ref "U1") (pin "2") (pinfunction "OUT_2") (pintype "passive"))
      (node (ref "U1") (pin "4") (pinfunction "OUT_4") (pintype "passive"))
      (node (ref "U2") (pin "2") (pinfunction "OUT_2") (pintype "passive"))
      (node (ref "U2") (pin "4") (pinfunction "OUT_4") (pintype "passive"))
      (node (ref "U3") (pin "2") (pinfunction "OUT_2") (pintype "passive"))
      (node (ref "U3") (pin "4") (pinfunction "OUT_4") (pintype "passive"))
    )
    (net (code "50") (name "Net-(DK1-A)") (class "Default")
      (node (ref "DK1") (pin "1") (pinfunction "A_1") (pintype "passive"))
      (node (ref "Q1") (pin "1") (pinfunction "C_1") (pintype "passive"))
      (node (ref "RE1") (pin "8") (pinfunction "GND_8") (pintype "passive"))
    )
    (net (code "51") (name "Net-(J1-Pad2)") (class "Default")
      (node (ref "J1") (pin "2") (pinfunction "2_2") (pintype "passive"))
      (node (ref "R1") (pin "2") (pinfunction "2_2") (pintype "passive"))
    )
    (net (code "52") (name "Net-(J2-Pad2)") (class "Default")
      (node (ref "J2") (pin "2") (pinfunction "2_2") (pintype "passive"))
      (node (ref "R2") (pin "2") (pinfunction "2_2") (pintype "passive"))
    )
    (net (code "53") (name "Net-(J3-Pad2)") (class "Default")
      (node (ref "J3") (pin "2") (pinfunction "2_2") (pintype "passive"))
      (node (ref "R3") (pin "2") (pinfunction "2_2") (pintype "passive"))
    )
    (net (code "54") (name "Net-(J4-Pad2)") (class "Default")
      (node (ref "J4") (pin "2") (pinfunction "2_2") (pintype "passive"))
      (node (ref "R4") (pin "2") (pinfunction "2_2") (pintype "passive"))
    )
    (net (code "55") (name "Net-(J5-Pad2)") (class "Default")
      (node (ref "J5") (pin "2") (pinfunction "2_2") (pintype "passive"))
      (node (ref "R5") (pin "2") (pinfunction "2_2") (pintype "passive"))
    )
    (net (code "56") (name "Net-(J6-Pad2)") (class "Default")
      (node (ref "J6") (pin "2") (pinfunction "2_2") (pintype "passive"))
      (node (ref "R6") (pin "2") (pinfunction "2_2") (pintype "passive"))
    )
    (net (code "57") (name "Net-(J7-Pad2)") (class "Default")
      (node (ref "J7") (pin "2") (pinfunction "2_2") (pintype "passive"))
      (node (ref "R7") (pin "2") (pinfunction "2_2") (pintype "passive"))
    )
    (net (code "58") (name "Net-(J8-Pad2)") (class "Default")
      (node (ref "J8") (pin "2") (pinfunction "2_2") (pintype "passive"))
      (node (ref "R8") (pin "2") (pinfunction "2_2") (pintype "passive"))
    )
    (net (code "59") (name "Net-(J9-Pad2)") (class "Default")
      (node (ref "J9") (pin "2") (pinfunction "2_2") (pintype "passive"))
      (node (ref "R9") (pin "2") (pinfunction "2_2") (pintype "passive"))
    )
    (net (code "60") (name "Net-(J10-Pad2)") (class "Default")
      (node (ref "J10") (pin "2") (pinfunction "2_2") (pintype "passive"))
      (node (ref "R10") (pin "2") (pinfunction "2_2") (pintype "passive"))
    )
    (net (code "61") (name "Net-(J11-Pad2)") (class "Default")
      (node (ref "J11") (pin "2") (pinfunction "2_2") (pintype "passive"))
      (node (ref "R11") (pin "2") (pinfunction "2_2") (pintype "passive"))
    )
    (net (code "62") (name "Net-(J12-Pad2)") (class "Default")
      (node (ref "J12") (pin "2") (pinfunction "2_2") (pintype "passive"))
      (node (ref "R12") (pin "2") (pinfunction "2_2") (pintype "passive"))
    )
    (net (code "63") (name "Net-(J13-Pad2)") (class "Default")
      (node (ref "J13") (pin "2") (pinfunction "2_2") (pintype "passive"))
      (node (ref "R13") (pin "2") (pinfunction "2_2") (pintype "passive"))
    )
    (net (code "64") (name "Net-(J14-Pad2)") (class "Default")
      (node (ref "J14") (pin "2") (pinfunction "2_2") (pintype "passive"))
      (node (ref "R14") (pin "2") (pinfunction "2_2") (pintype "passive"))
    )
    (net (code "65") (name "Net-(J15-Pad2)") (class "Default")
      (node (ref "J15") (pin "2") (pinfunction "2_2") (pintype "passive"))
      (node (ref "R15") (pin "2") (pinfunction "2_2") (pintype "passive"))
    )
    (net (code "66") (name "Net-(J16-Pad2)") (class "Default")
      (node (ref "J16") (pin "2") (pinfunction "2_2") (pintype "passive"))
      (node (ref "R16") (pin "2") (pinfunction "2_2") (pintype "passive"))
    )
    (net (code "67") (name "Net-(J17-Pad2)") (class "Default")
      (node (ref "J17") (pin "2") (pinfunction "2_2") (pintype "passive"))
      (node (ref "R17") (pin "2") (pinfunction "2_2") (pintype "passive"))
    )
    (net (code "68") (name "Net-(J18-Pad2)") (class "Default")
      (node (ref "J18") (pin "2") (pinfunction "2_2") (pintype "passive"))
      (node (ref "R18") (pin "2") (pinfunction "2_2") (pintype "passive"))
    )
    (net (code "69") (name "Net-(J19-Pad2)") (class "Default")
      (node (ref "J19") (pin "2") (pinfunction "2_2") (pintype "passive"))
      (node (ref "R19") (pin "2") (pinfunction "2_2") (pintype "passive"))
    )
    (net (code "70") (name "Net-(J20-Pad2)") (class "Default")
      (node (ref "J20") (pin "2") (pinfunction "2_2") (pintype "passive"))
      (node (ref "R20") (pin "2") (pinfunction "2_2") (pintype "passive"))
    )
    (net (code "71") (name "Net-(J21-Pad2)") (class "Default")
      (node (ref "J21") (pin "2") (pinfunction "2_2") (pintype "passive"))
      (node (ref "R21") (pin "2") (pinfunction "2_2") (pintype "passive"))
    )
    (net (code "72") (name "Net-(J22-Pad2)") (class "Default")
      (node (ref "J22") (pin "2") (pinfunction "2_2") (pintype "passive"))
      (node (ref "R22") (pin "2") (pinfunction "2_2") (pintype "passive"))
    )
    (net (code "73") (name "Net-(J23-Pad2)") (class "Default")
      (node (ref "J23") (pin "2") (pinfunction "2_2") (pintype "passive"))
      (node (ref "R23") (pin "2") (pinfunction "2_2") (pintype "passive"))
    )
    (net (code "74") (name "Net-(J24-Pad2)") (class "Default")
      (node (ref "J24") (pin "2") (pinfunction "2_2") (pintype "passive"))
      (node (ref "R24") (pin "2") (pinfunction "2_2") (pintype "passive"))
    )
    (net (code "75") (name "Net-(J25-Pad2)") (class "Default")
      (node (ref "J25") (pin "2") (pinfunction "2_2") (pintype "passive"))
      (node (ref "R25") (pin "2") (pinfunction "2_2") (pintype "passive"))
    )
    (net (code "76") (name "Net-(J26-Pad2)") (class "Default")
      (node (ref "J26") (pin "2") (pinfunction "2_2") (pintype "passive"))
      (node (ref "R26") (pin "2") (pinfunction "2_2") (pintype "passive"))
    )
    (net (code "77") (name "Net-(LED1-K)") (class "Default")
      (node (ref "LED1") (pin "2") (pinfunction "K_2") (pintype "passive"))
      (node (ref "R31") (pin "1") (pinfunction "1_1") (pintype "passive"))
    )
    (net (code "78") (name "Net-(LED2-K)") (class "Default")
      (node (ref "LED2") (pin "2") (pinfunction "K_2") (pintype "passive"))
      (node (ref "R30") (pin "2") (pinfunction "2_2") (pintype "passive"))
    )
    (net (code "79") (name "Net-(LED3-K)") (class "Default")
      (node (ref "LED3") (pin "2") (pinfunction "K_2") (pintype "passive"))
      (node (ref "R32") (pin "1") (pinfunction "1_1") (pintype "passive"))
    )
    (net (code "80") (name "Net-(P1-Pad2)") (class "Default")
      (node (ref "P1") (pin "2") (pinfunction "2_2") (pintype "passive"))
      (node (ref "RE1") (pin "3") (pinfunction "3_3") (pintype "passive"))
    )
    (net (code "81") (name "Net-(P1-Pad3)") (class "Default")
      (node (ref "P1") (pin "3") (pinfunction "3_3") (pintype "passive"))
      (node (ref "RE1") (pin "4") (pinfunction "4_4") (pintype "passive"))
    )
    (net (code "82") (name "Net-(P14-Pad1)") (class "Default")
      (node (ref "P14") (pin "1") (pinfunction "1_1") (pintype "passive"))
      (node (ref "Rf2") (pin "1") (pinfunction "1_1") (pintype "passive"))
    )
    (net (code "83") (name "Net-(P14-Pad2)") (class "Default")
      (node (ref "P14") (pin "2") (pinfunction "2_2") (pintype "passive"))
      (node (ref "Rf2") (pin "2") (pinfunction "2_2") (pintype "passive"))
    )
    (net (code "84") (name "Net-(P14-Pad3)") (class "Default")
      (node (ref "P14") (pin "3") (pinfunction "3_3") (pintype "passive"))
      (node (ref "Rf2") (pin "3") (pinfunction "3_3") (pintype "passive"))
    )
    (net (code "85") (name "Net-(P14-Pad4)") (class "Default")
      (node (ref "P14") (pin "4") (pinfunction "4_4") (pintype "passive"))
      (node (ref "Rf2") (pin "4") (pinfunction "4_4") (pintype "passive"))
    )
    (net (code "86") (name "Net-(P14-Pad5)") (class "Default")
      (node (ref "P14") (pin "5") (pinfunction "5_5") (pintype "passive"))
      (node (ref "Rf1") (pin "1") (pinfunction "1_1") (pintype "passive"))
    )
    (net (code "87") (name "Net-(P14-Pad6)") (class "Default")
      (node (ref "P14") (pin "6") (pinfunction "6_6") (pintype "passive"))
      (node (ref "Rf1") (pin "2") (pinfunction "2_2") (pintype "passive"))
    )
    (net (code "88") (name "Net-(P14-Pad7)") (class "Default")
      (node (ref "P14") (pin "7") (pinfunction "7_7") (pintype "passive"))
      (node (ref "Rf1") (pin "3") (pinfunction "3_3") (pintype "passive"))
    )
    (net (code "89") (name "Net-(P14-Pad8)") (class "Default")
      (node (ref "P14") (pin "8") (pinfunction "8_8") (pintype "passive"))
      (node (ref "Rf1") (pin "4") (pinfunction "4_4") (pintype "passive"))
    )
    (net (code "90") (name "Net-(Q1-B)") (class "Default")
      (node (ref "Q1") (pin "2") (pinfunction "B_2") (pintype "passive"))
      (node (ref "R27") (pin "2") (pinfunction "2_2") (pintype "passive"))
      (node (ref "R29") (pin "1") (pinfunction "1_1") (pintype "passive"))
    )
    (net (code "91") (name "Net-(R28-Pad1)") (class "Default")
      (node (ref "R28") (pin "1") (pinfunction "1_1") (pintype "passive"))
      (node (ref "RE1") (pin "5") (pinfunction "5_5") (pintype "passive"))
    )
    (net (code "92") (name "Net-(RE1-COM)") (class "Default")
      (node (ref "P1") (pin "1") (pinfunction "1_1") (pintype "passive"))
      (node (ref "RE1") (pin "2") (pinfunction "COM_2") (pintype "passive"))
    )
    (net (code "93") (name "VCC3.3") (class "Default")
      (node (ref "D27") (pin "2") (pinfunction "K_2") (pintype "passive"))
      (node (ref "D28") (pin "2") (pinfunction "K_2") (pintype "passive"))
      (node (ref "F2") (pin "2") (pinfunction "2_2") (pintype "passive"))
      (node (ref "LED3") (pin "1") (pinfunction "A_1") (pintype "passive"))
      (node (ref "P10") (pin "1") (pinfunction "1_1") (pintype "passive"))
      (node (ref "P11") (pin "1") (pinfunction "1_1") (pintype "passive"))
      (node (ref "P13") (pin "1") (pinfunction "1_1") (pintype "passive"))
      (node (ref "P15") (pin "3") (pinfunction "3_3") (pintype "passive"))
      (node (ref "P15") (pin "7") (pinfunction "7_7") (pintype "passive"))
      (node (ref "P16") (pin "1") (pinfunction "1_1") (pintype "passive"))
      (node (ref "P3") (pin "9") (pinfunction "9_9") (pintype "passive"))
      (node (ref "P4") (pin "5") (pinfunction "5_5") (pintype "passive"))
      (node (ref "P6") (pin "1") (pinfunction "1_1") (pintype "passive"))
      (node (ref "P8") (pin "1") (pinfunction "1_1") (pintype "passive"))
    )
    (net (code "94") (name "VCC5") (class "Default")
      (node (ref "DK1") (pin "2") (pinfunction "K_2") (pintype "passive"))
      (node (ref "F1") (pin "2") (pinfunction "2_2") (pintype "passive"))
      (node (ref "LED2") (pin "1") (pinfunction "A_1") (pintype "passive"))
      (node (ref "P15") (pin "2") (pinfunction "2_2") (pintype "passive"))
      (node (ref "P15") (pin "6") (pinfunction "6_6") (pintype "passive"))
      (node (ref "RE1") (pin "1") (pinfunction "VCC_1") (pintype "passive"))
      (node (ref "U1") (pin "3") (pinfunction "IN_3") (pintype "passive"))
      (node (ref "U2") (pin "3") (pinfunction "IN_3") (pintype "passive"))
      (node (ref "U3") (pin "3") (pinfunction "IN_3") (pintype "passive"))
    )
    (net (code "95") (name "VCC24") (class "Default")
      (node (ref "C2") (pin "1") (pinfunction "1_1") (pintype "passive"))
      (node (ref "C3") (pin "1") (pinfunction "1_1") (pintype "passive"))
      (node (ref "J1") (pin "1") (pinfunction "1_1") (pintype "passive"))
      (node (ref "J10") (pin "1") (pinfunction "1_1") (pintype "passive"))
      (node (ref "J11") (pin "1") (pinfunction "1_1") (pintype "passive"))
      (node (ref "J12") (pin "1") (pinfunction "1_1") (pintype "passive"))
      (node (ref "J13") (pin "1") (pinfunction "1_1") (pintype "passive"))
      (node (ref "J14") (pin "1") (pinfunction "1_1") (pintype "passive"))
      (node (ref "J15") (pin "1") (pinfunction "1_1") (pintype "passive"))
      (node (ref "J16") (pin "1") (pinfunction "1_1") (pintype "passive"))
      (node (ref "J17") (pin "1") (pinfunction "1_1") (pintype "passive"))
      (node (ref "J18") (pin "1") (pinfunction "1_1") (pintype "passive"))
      (node (ref "J19") (pin "1") (pinfunction "1_1") (pintype "passive"))
      (node (ref "J2") (pin "1") (pinfunction "1_1") (pintype "passive"))
      (node (ref "J20") (pin "1") (pinfunction "1_1") (pintype "passive"))
      (node (ref "J21") (pin "1") (pinfunction "1_1") (pintype "passive"))
      (node (ref "J22") (pin "1") (pinfunction "1_1") (pintype "passive"))
      (node (ref "J23") (pin "1") (pinfunction "1_1") (pintype "passive"))
      (node (ref "J24") (pin "1") (pinfunction "1_1") (pintype "passive"))
      (node (ref "J25") (pin "1") (pinfunction "1_1") (pintype "passive"))
      (node (ref "J26") (pin "1") (pinfunction "1_1") (pintype "passive"))
      (node (ref "J3") (pin "1") (pinfunction "1_1") (pintype "passive"))
      (node (ref "J4") (pin "1") (pinfunction "1_1") (pintype "passive"))
      (node (ref "J5") (pin "1") (pinfunction "1_1") (pintype "passive"))
      (node (ref "J6") (pin "1") (pinfunction "1_1") (pintype "passive"))
      (node (ref "J7") (pin "1") (pinfunction "1_1") (pintype "passive"))
      (node (ref "J8") (pin "1") (pinfunction "1_1") (pintype "passive"))
      (node (ref "J9") (pin "1") (pinfunction "1_1") (pintype "passive"))
      (node (ref "LED1") (pin "1") (pinfunction "A_1") (pintype "passive"))
      (node (ref "P15") (pin "1") (pinfunction "1_1") (pintype "passive"))
      (node (ref "P15") (pin "5") (pinfunction "5_5") (pintype "passive"))
      (node (ref "P9") (pin "1") (pinfunction "1_1") (pintype "passive"))
      (node (ref "RE1") (pin "7") (pinfunction "7_7") (pintype "passive"))
    )
    (net (code "96") (name "unconnected-(RE1-Pad6)") (class "Default")
      (node (ref "RE1") (pin "6") (pinfunction "6_6") (pintype "passive+no_connect"))
    )
  )
)
